# LPCB235_-_RM48_-_N2HET.net
KiCad netlist of a schematic drawn in Altium Designer
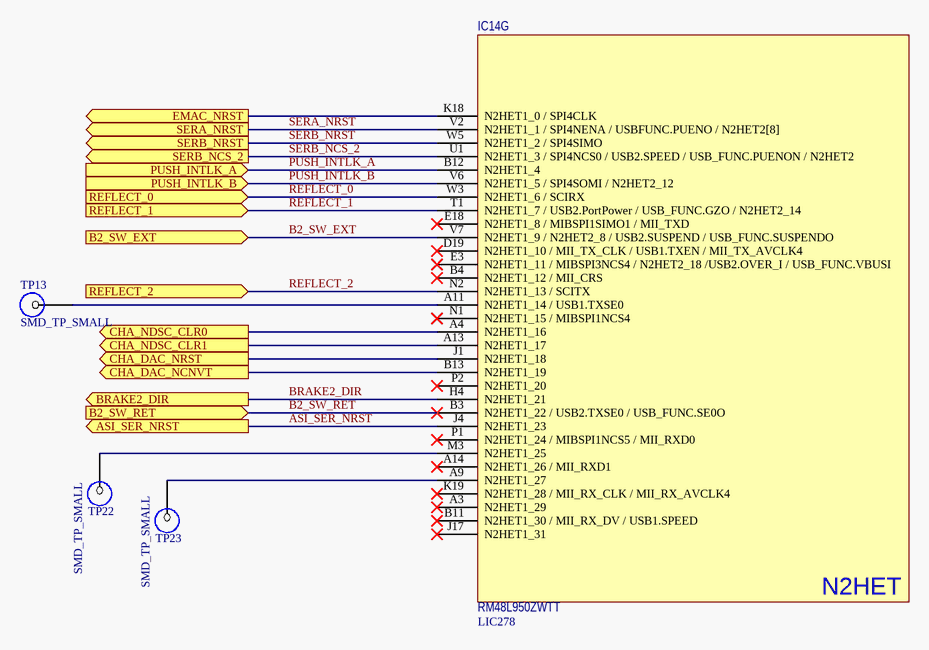
[diagram p0: LPCB235 - RM48 - N2HET.SchDoc]

(export (version "E")
  (design (tool "Eeschema 10.0.6"))
  (components
    (comp (ref "IC14")
      (value "RM48L950ZWTT")
      (footprint "LFP054__ZWT (S-PBGA-N337)")
      (description "IC, CPU, RM48 Safety CPU, SMD NFBGA337 [LIC278]")
      (fields (field (name "LDL_NUMBER") "LIC278"))
      (libsource (lib "LDL_Semiconductors") (part "RM48L950ZWTT"))
    )
    (comp (ref "TP13")
      (value "SMD_TP_SMALL")
      (footprint "SMD-TP-SMALL")
      (description "SMD Test Point")
      (libsource (lib "LDL_Connectors") (part "SMD_TP_SMALL"))
    )
    (comp (ref "TP22")
      (value "SMD_TP_SMALL")
      (footprint "SMD-TP-SMALL")
      (description "SMD Test Point")
      (libsource (lib "LDL_Connectors") (part "SMD_TP_SMALL"))
    )
    (comp (ref "TP23")
      (value "SMD_TP_SMALL")
      (footprint "SMD-TP-SMALL")
      (description "SMD Test Point")
      (libsource (lib "LDL_Connectors") (part "SMD_TP_SMALL"))
    )
  )
  (nets
    (net (code "1") (name "/ASI_SER_NRST") (class "Default")
      (node (ref "IC14") (pin "J4") (pinfunction "N2HET1_23_J4") (pintype "passive"))
    )
    (net (code "2") (name "/B2_SW_EXT") (class "Default")
      (node (ref "IC14") (pin "V7") (pinfunction "N2HET1_9_/_N2HET2_8_/_USB2.SUSPEND_/_USB_FUNC.SUSPENDO_V7") (pintype "passive"))
    )
    (net (code "3") (name "/B2_SW_RET") (class "Default")
      (node (ref "IC14") (pin "B3") (pinfunction "N2HET1_22_/_USB2.TXSE0_/_USB_FUNC.SE0O_B3") (pintype "passive+no_connect"))
    )
    (net (code "4") (name "/BRAKE2_DIR") (class "Default")
      (node (ref "IC14") (pin "H4") (pinfunction "N2HET1_21_H4") (pintype "passive"))
    )
    (net (code "5") (name "/CHA_DAC_NCNVT") (class "Default")
      (node (ref "IC14") (pin "B13") (pinfunction "N2HET1_19_B13") (pintype "passive"))
    )
    (net (code "6") (name "/CHA_DAC_NRST") (class "Default")
      (node (ref "IC14") (pin "J1") (pinfunction "N2HET1_18_J1") (pintype "passive"))
    )
    (net (code "7") (name "/CHA_NDSC_CLR0") (class "Default")
      (node (ref "IC14") (pin "A4") (pinfunction "N2HET1_16_A4") (pintype "passive"))
    )
    (net (code "8") (name "/CHA_NDSC_CLR1") (class "Default")
      (node (ref "IC14") (pin "A13") (pinfunction "N2HET1_17_A13") (pintype "passive"))
    )
    (net (code "9") (name "/EMAC_NRST") (class "Default")
      (node (ref "IC14") (pin "K18") (pinfunction "N2HET1_0_/_SPI4CLK_K18") (pintype "passive"))
    )
    (net (code "10") (name "/PUSH_INTLK_A") (class "Default")
      (node (ref "IC14") (pin "B12") (pinfunction "N2HET1_4_B12") (pintype "passive"))
    )
    (net (code "11") (name "/PUSH_INTLK_B") (class "Default")
      (node (ref "IC14") (pin "V6") (pinfunction "N2HET1_5_/_SPI4SOMI_/_N2HET2_12_V6") (pintype "passive"))
    )
    (net (code "12") (name "/REFLECT_0") (class "Default")
      (node (ref "IC14") (pin "W3") (pinfunction "N2HET1_6_/_SCIRX_W3") (pintype "passive"))
    )
    (net (code "13") (name "/REFLECT_1") (class "Default")
      (node (ref "IC14") (pin "T1") (pinfunction "N2HET1_7_/_USB2.PortPower_/_USB_FUNC.GZO_/_N2HET2_14_T1") (pintype "passive"))
    )
    (net (code "14") (name "/REFLECT_2") (class "Default")
      (node (ref "IC14") (pin "N2") (pinfunction "N2HET1_13_/_SCITX_N2") (pintype "passive"))
    )
    (net (code "15") (name "/SERA_NRST") (class "Default")
      (node (ref "IC14") (pin "V2") (pinfunction "N2HET1_1_/_SPI4NENA_/_USBFUNC.PUENO_/_N2HET2[8]_V2") (pintype "passive"))
    )
    (net (code "16") (name "/SERB_NCS_2") (class "Default")
      (node (ref "IC14") (pin "U1") (pinfunction "N2HET1_3_/_SPI4NCS0_/_USB2.SPEED_/_USB_FUNC.PUENON_/_N2HET2_U1") (pintype "passive"))
    )
    (net (code "17") (name "/SERB_NRST") (class "Default")
      (node (ref "IC14") (pin "W5") (pinfunction "N2HET1_2_/_SPI4SIMO_W5") (pintype "passive"))
    )
    (net (code "18") (name "Net-(IC14G-N2HET1_14_{slash}_USB1.TXSE0)") (class "Default")
      (node (ref "IC14") (pin "A11") (pinfunction "N2HET1_14_/_USB1.TXSE0_A11") (pintype "passive"))
      (node (ref "TP13") (pin "1") (pintype "passive"))
    )
    (net (code "19") (name "Net-(IC14G-N2HET1_25)") (class "Default")
      (node (ref "IC14") (pin "M3") (pinfunction "N2HET1_25_M3") (pintype "passive"))
      (node (ref "TP22") (pin "1") (pintype "passive"))
    )
    (net (code "20") (name "Net-(IC14G-N2HET1_27)") (class "Default")
      (node (ref "IC14") (pin "A9") (pinfunction "N2HET1_27_A9") (pintype "passive"))
      (node (ref "TP23") (pin "1") (pintype "passive"))
    )
    (net (code "21") (name "unconnected-(IC14G-N2HET1_8_{slash}_MIBSPI1SIMO1_{slash}_MII_TXD-PadE18)") (class "Default")
      (node (ref "IC14") (pin "E18") (pinfunction "N2HET1_8_/_MIBSPI1SIMO1_/_MII_TXD_E18") (pintype "passive+no_connect"))
    )
    (net (code "22") (name "unconnected-(IC14G-N2HET1_10_{slash}_MII_TX_CLK_{slash}_USB1.TXEN_{slash}_MII_TX_AVCLK4-PadD19)") (class "Default")
      (node (ref "IC14") (pin "D19") (pinfunction "N2HET1_10_/_MII_TX_CLK_/_USB1.TXEN_/_MII_TX_AVCLK4_D19") (pintype "passive+no_connect"))
    )
    (net (code "23") (name "unconnected-(IC14G-N2HET1_11_{slash}_MIBSPI3NCS4_{slash}_N2HET2_18_{slash}USB2.OVER_I_{slash}_USB_FUNC.VBUSI-PadE3)") (class "Default")
      (node (ref "IC14") (pin "E3") (pinfunction "N2HET1_11_/_MIBSPI3NCS4_/_N2HET2_18_/USB2.OVER_I_/_USB_FUNC.VBUSI_E3") (pintype "passive+no_connect"))
    )
    (net (code "24") (name "unconnected-(IC14G-N2HET1_12_{slash}_MII_CRS-PadB4)") (class "Default")
      (node (ref "IC14") (pin "B4") (pinfunction "N2HET1_12_/_MII_CRS_B4") (pintype "passive+no_connect"))
    )
    (net (code "25") (name "unconnected-(IC14G-N2HET1_15_{slash}_MIBSPI1NCS4-PadN1)") (class "Default")
      (node (ref "IC14") (pin "N1") (pinfunction "N2HET1_15_/_MIBSPI1NCS4_N1") (pintype "passive+no_connect"))
    )
    (net (code "26") (name "unconnected-(IC14G-N2HET1_20-PadP2)") (class "Default")
      (node (ref "IC14") (pin "P2") (pinfunction "N2HET1_20_P2") (pintype "passive+no_connect"))
    )
    (net (code "27") (name "unconnected-(IC14G-N2HET1_24_{slash}_MIBSPI1NCS5_{slash}_MII_RXD0-PadP1)") (class "Default")
      (node (ref "IC14") (pin "P1") (pinfunction "N2HET1_24_/_MIBSPI1NCS5_/_MII_RXD0_P1") (pintype "passive+no_connect"))
    )
    (net (code "28") (name "unconnected-(IC14G-N2HET1_26_{slash}_MII_RXD1-PadA14)") (class "Default")
      (node (ref "IC14") (pin "A14") (pinfunction "N2HET1_26_/_MII_RXD1_A14") (pintype "passive+no_connect"))
    )
    (net (code "29") (name "unconnected-(IC14G-N2HET1_28_{slash}_MII_RX_CLK_{slash}_MII_RX_AVCLK4-PadK19)") (class "Default")
      (node (ref "IC14") (pin "K19") (pinfunction "N2HET1_28_/_MII_RX_CLK_/_MII_RX_AVCLK4_K19") (pintype "passive+no_connect"))
    )
    (net (code "30") (name "unconnected-(IC14G-N2HET1_29-PadA3)") (class "Default")
      (node (ref "IC14") (pin "A3") (pinfunction "N2HET1_29_A3") (pintype "passive+no_connect"))
    )
    (net (code "31") (name "unconnected-(IC14G-N2HET1_30_{slash}_MII_RX_DV_{slash}_USB1.SPEED-PadB11)") (class "Default")
      (node (ref "IC14") (pin "B11") (pinfunction "N2HET1_30_/_MII_RX_DV_/_USB1.SPEED_B11") (pintype "passive+no_connect"))
    )
    (net (code "32") (name "unconnected-(IC14G-N2HET1_31-PadJ17)") (class "Default")
      (node (ref "IC14") (pin "J17") (pinfunction "N2HET1_31_J17") (pintype "passive+no_connect"))
    )
  )
)
